# Ref_Mult.net
KiCad netlist of a schematic drawn in Altium Designer
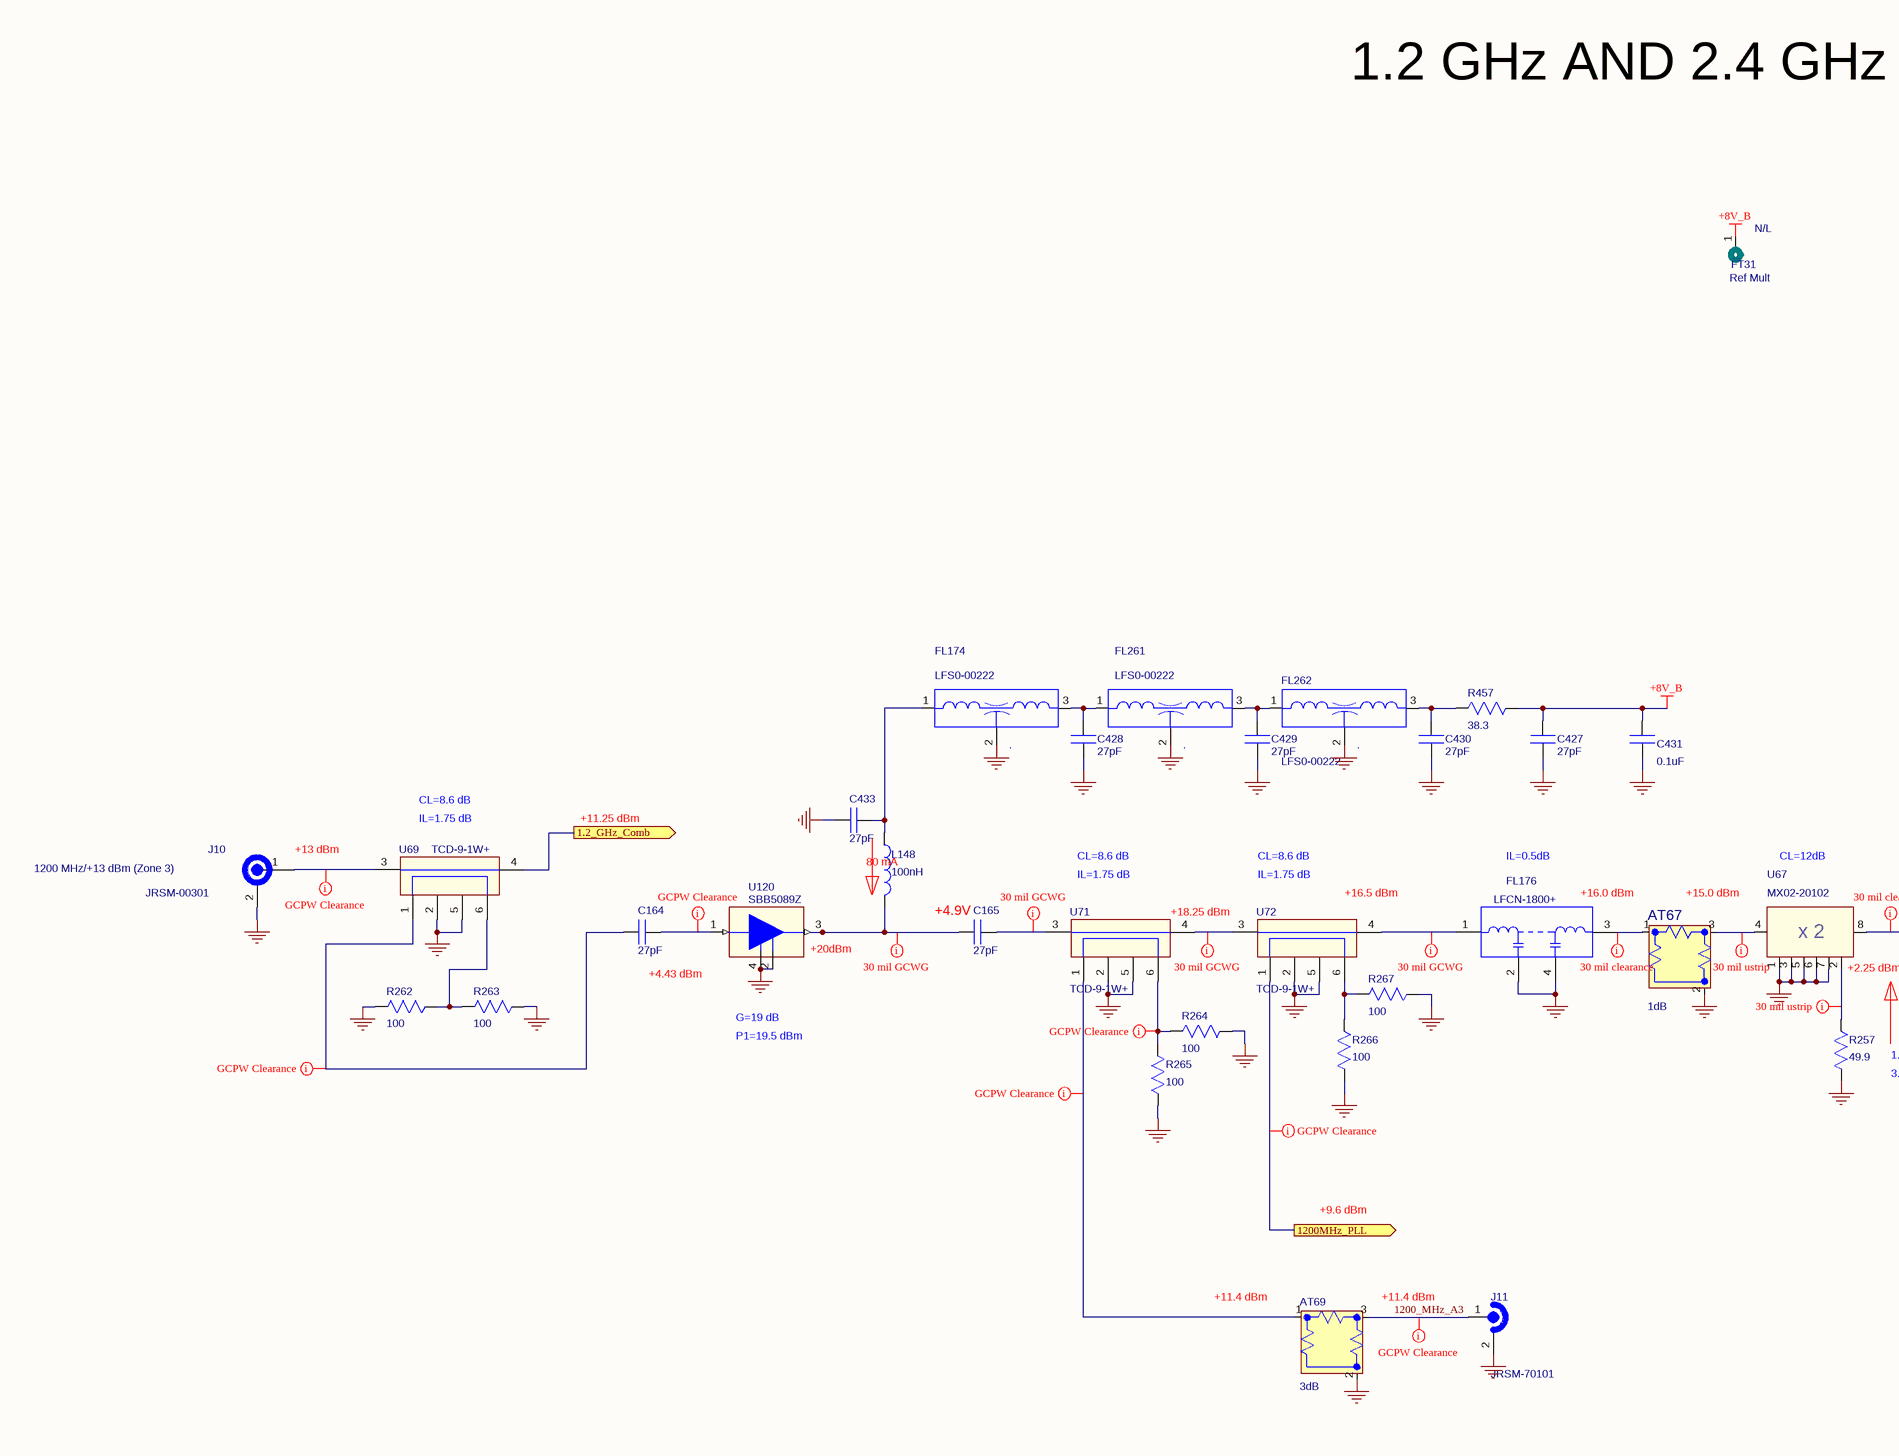
[diagram p0: Ref Mult.SchDoc, left]
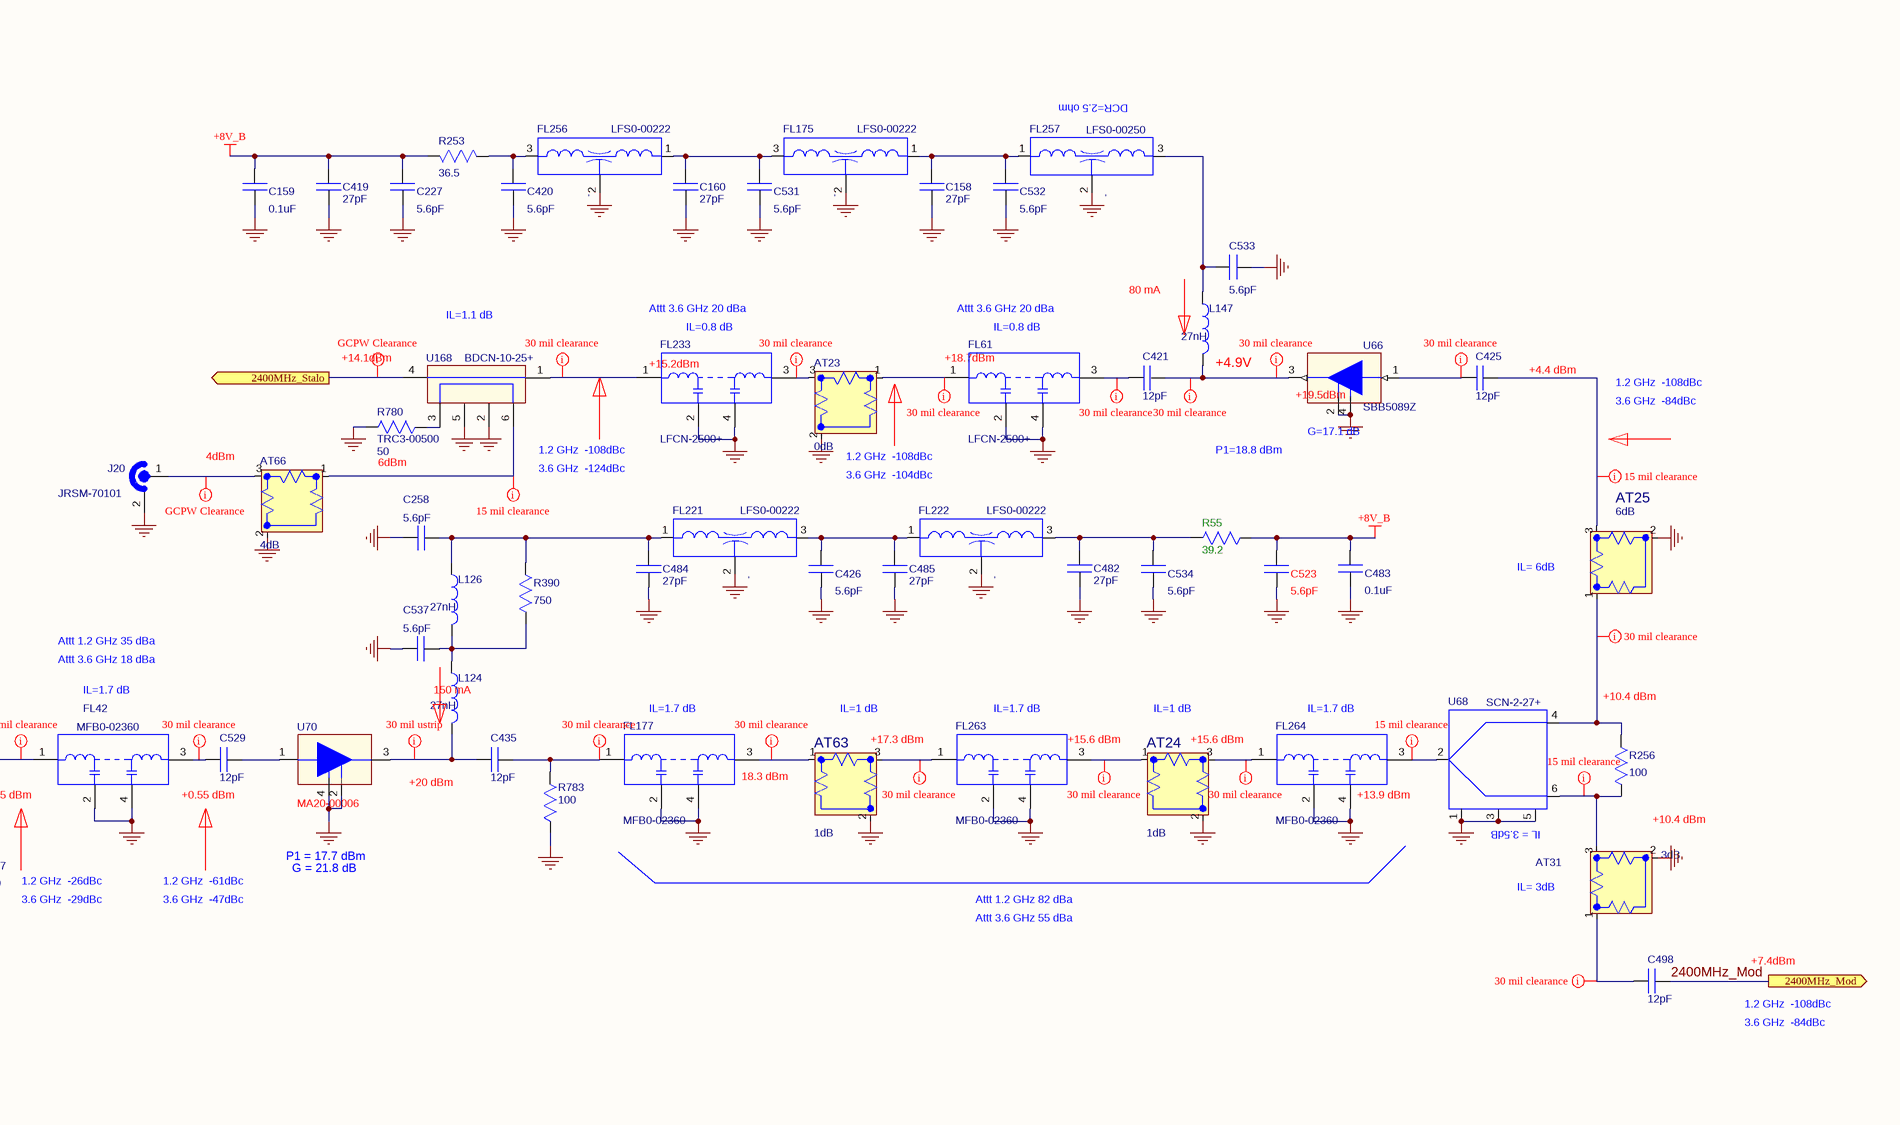
[diagram p1: Ref Mult.SchDoc, right]

(export (version "E")
  (design (tool "Eeschema 10.0.6"))
  (components
    (comp (ref "AT23")
      (value "0dB")
      (footprint "ATTN-IMS-0805")
      (description "PAD;CHIP;0dB;+/-.3dB;.08 x .05;50 OHM;FACE DOWN")
      (fields (field (name "APPROVED") "CL"))
      (libsource (lib "Giga-tronics") (part "MPFC-A1000"))
    )
    (comp (ref "AT24")
      (value "1dB")
      (footprint "ATTN-IMS-0805")
      (description "PAD;CHIP;1dB;+/-.3dB;.08 x .05;50 OHM;FACE DOWN")
      (fields (field (name "APPROVED") "CL"))
      (libsource (lib "Giga-tronics") (part "MPFC-A1001"))
    )
    (comp (ref "AT25")
      (value "6dB")
      (footprint "ATTN-IMS-0805")
      (description "PAD;CHIP;6dB;+/-.3dB;.08 x .05;50 OHM;FACE DOWN")
      (fields (field (name "APPROVED") "CL"))
      (libsource (lib "Giga-tronics") (part "MPFC-A1006"))
    )
    (comp (ref "AT31")
      (value "3dB")
      (footprint "ATTN-IMS-0805")
      (description "PAD;CHIP;3dB;+/-.3dB;.08 x .05;50 OHM;FACE DOWN")
      (fields (field (name "APPROVED") "CL"))
      (libsource (lib "") (part "MPFC-A1003_1"))
    )
    (comp (ref "AT63")
      (value "1dB")
      (footprint "ATTN-IMS-0805")
      (description "PAD;CHIP;1dB;+/-.3dB;.08 x .05;50 OHM;FACE DOWN")
      (fields (field (name "APPROVED") "CL"))
      (libsource (lib "Giga-tronics") (part "MPFC-A1001"))
    )
    (comp (ref "AT66")
      (value "4dB")
      (footprint "ATTN-IMS-0805")
      (description "PAD;CHIP;4dB;+/-.3dB;.08 x .05;50 OHM;FACE DOWN")
      (fields (field (name "APPROVED") "CL"))
      (libsource (lib "Giga-tronics") (part "MPFC-A1004"))
    )
    (comp (ref "AT67")
      (value "1dB")
      (footprint "ATTN-IMS-0805")
      (description "PAD;CHIP;1dB;+/-.3dB;.08 x .05;50 OHM;FACE DOWN")
      (fields (field (name "APPROVED") "CL"))
      (libsource (lib "Giga-tronics") (part "MPFC-A1001"))
    )
    (comp (ref "AT69")
      (value "3dB")
      (footprint "ATTN-IMS-0805")
      (description "PAD;CHIP;3dB;+/-.3dB;.08 x .05;50 OHM;FACE DOWN")
      (fields (field (name "APPROVED") "CL"))
      (libsource (lib "Giga-tronics") (part "MPFC-A1003"))
    )
    (comp (ref "C158")
      (value "27pF")
      (footprint "CAP-0402-N")
      (description "27 PF;5%;COG;>50V;CHIP;0402")
      (fields (field (name "APPROVED") "CL"))
      (libsource (lib "Giga-tronics") (part "CK40-00270"))
    )
    (comp (ref "C159")
      (value "0.1uF")
      (footprint "CAP-0603-H035-N")
      (description ".1UF;10%;X7R;16V;CHIP;0603")
      (fields (field (name "APPROVED") "CL"))
      (libsource (lib "Giga-tronics") (part "CK45-04100"))
    )
    (comp (ref "C160")
      (value "27pF")
      (footprint "CAP-0402-N")
      (description "27 PF;5%;COG;>50V;CHIP;0402")
      (fields (field (name "APPROVED") "CL"))
      (libsource (lib "Giga-tronics") (part "CK40-00270"))
    )
    (comp (ref "C164")
      (value "27pF")
      (footprint "CAP-0402-N")
      (description "27 PF;5%;COG;>50V;CHIP;0402")
      (fields (field (name "APPROVED") "CL"))
      (libsource (lib "Giga-tronics") (part "CK40-00270"))
    )
    (comp (ref "C165")
      (value "27pF")
      (footprint "CAP-0402-N")
      (description "27 PF;5%;COG;>50V;CHIP;0402")
      (fields (field (name "APPROVED") "CL"))
      (libsource (lib "Giga-tronics") (part "CK40-00270"))
    )
    (comp (ref "C227")
      (value "5.6pF")
      (footprint "CAP-0402-RF")
      (description "5.6 PF;200V;.1PF;HIGH Q;SMT;CERAMIC;0402")
      (fields (field (name "APPROVED") "CL"))
      (libsource (lib "Giga-tronics") (part "CK41-00056"))
    )
    (comp (ref "C258")
      (value "5.6pF")
      (footprint "CAP-0402-RF")
      (description "5.6 PF;200V;.1PF;HIGH Q;SMT;CERAMIC;0402")
      (fields (field (name "APPROVED") "CL"))
      (libsource (lib "Giga-tronics") (part "CK41-00056"))
    )
    (comp (ref "C419")
      (value "27pF")
      (footprint "CAP-0402-N")
      (description "27 PF;5%;COG;>50V;CHIP;0402")
      (fields (field (name "APPROVED") "CL"))
      (libsource (lib "Giga-tronics") (part "CK40-00270"))
    )
    (comp (ref "C420")
      (value "5.6pF")
      (footprint "CAP-0402-RF")
      (description "5.6 PF;200V;.1PF;HIGH Q;SMT;CERAMIC;0402")
      (fields (field (name "APPROVED") "CL"))
      (libsource (lib "Giga-tronics") (part "CK41-00056"))
    )
    (comp (ref "C421")
      (value "12pF")
      (footprint "CAP-0402-N")
      (description "12 PF;5%;COG;>50V;CHIP;0402")
      (fields (field (name "APPROVED") "CL"))
      (libsource (lib "Giga-tronics") (part "CK40-00120"))
    )
    (comp (ref "C425")
      (value "12pF")
      (footprint "CAP-0402-N")
      (description "12 PF;5%;COG;>50V;CHIP;0402")
      (fields (field (name "APPROVED") "CL"))
      (libsource (lib "Giga-tronics") (part "CK40-00120"))
    )
    (comp (ref "C426")
      (value "5.6pF")
      (footprint "CAP-0402-RF")
      (description "5.6 PF;200V;.1PF;HIGH Q;SMT;CERAMIC;0402")
      (fields (field (name "APPROVED") "CL"))
      (libsource (lib "Giga-tronics") (part "CK41-00056"))
    )
    (comp (ref "C427")
      (value "27pF")
      (footprint "CAP-0402-N")
      (description "27 PF;5%;COG;>50V;CHIP;0402")
      (fields (field (name "APPROVED") "CL"))
      (libsource (lib "Giga-tronics") (part "CK40-00270"))
    )
    (comp (ref "C428")
      (value "27pF")
      (footprint "CAP-0402-N")
      (description "27 PF;5%;COG;>50V;CHIP;0402")
      (fields (field (name "APPROVED") "CL"))
      (libsource (lib "Giga-tronics") (part "CK40-00270"))
    )
    (comp (ref "C429")
      (value "27pF")
      (footprint "CAP-0402-N")
      (description "27 PF;5%;COG;>50V;CHIP;0402")
      (fields (field (name "APPROVED") "CL"))
      (libsource (lib "Giga-tronics") (part "CK40-00270"))
    )
    (comp (ref "C430")
      (value "27pF")
      (footprint "CAP-0402-N")
      (description "27 PF;5%;COG;>50V;CHIP;0402")
      (fields (field (name "APPROVED") "CL"))
      (libsource (lib "Giga-tronics") (part "CK40-00270"))
    )
    (comp (ref "C431")
      (value "0.1uF")
      (footprint "CAP-0603-H035-N")
      (description ".1UF;10%;X7R;16V;CHIP;0603")
      (fields (field (name "APPROVED") "CL"))
      (libsource (lib "Giga-tronics") (part "CK45-04100"))
    )
    (comp (ref "C433")
      (value "27pF")
      (footprint "CAP-0402-N")
      (description "27 PF;5%;COG;>50V;CHIP;0402")
      (fields (field (name "APPROVED") "CL"))
      (libsource (lib "Giga-tronics") (part "CK40-00270"))
    )
    (comp (ref "C435")
      (value "12pF")
      (footprint "CAP-0402-N")
      (description "12 PF;5%;COG;>50V;CHIP;0402")
      (fields (field (name "APPROVED") "CL"))
      (libsource (lib "Giga-tronics") (part "CK40-00120"))
    )
    (comp (ref "C482")
      (value "27pF")
      (footprint "CAP-0402-N")
      (description "27 PF;5%;COG;>50V;CHIP;0402")
      (fields (field (name "APPROVED") "CL"))
      (libsource (lib "Giga-tronics") (part "CK40-00270"))
    )
    (comp (ref "C483")
      (value "0.1uF")
      (footprint "CAP-0603-H035-N")
      (description ".1UF;10%;X7R;16V;CHIP;0603")
      (fields (field (name "APPROVED") "CL"))
      (libsource (lib "Giga-tronics") (part "CK45-04100"))
    )
    (comp (ref "C484")
      (value "27pF")
      (footprint "CAP-0402-N")
      (description "27 PF;5%;COG;>50V;CHIP;0402")
      (fields (field (name "APPROVED") "CL"))
      (libsource (lib "Giga-tronics") (part "CK40-00270"))
    )
    (comp (ref "C485")
      (value "27pF")
      (footprint "CAP-0402-N")
      (description "27 PF;5%;COG;>50V;CHIP;0402")
      (fields (field (name "APPROVED") "CL"))
      (libsource (lib "Giga-tronics") (part "CK40-00270"))
    )
    (comp (ref "C498")
      (value "12pF")
      (footprint "CAP-0402-N")
      (description "12 PF;5%;COG;>50V;CHIP;0402")
      (fields (field (name "APPROVED") "CL"))
      (libsource (lib "Giga-tronics") (part "CK40-00120"))
    )
    (comp (ref "C523")
      (value "5.6pF")
      (footprint "CAP-0402-RF")
      (description "5.6 PF;200V;.1PF;HIGH Q;SMT;CERAMIC;0402")
      (fields (field (name "APPROVED") "CL"))
      (libsource (lib "Giga-tronics") (part "CK41-00056"))
    )
    (comp (ref "C529")
      (value "12pF")
      (footprint "CAP-0402-N")
      (description "12 PF;5%;COG;>50V;CHIP;0402")
      (fields (field (name "APPROVED") "CL"))
      (libsource (lib "Giga-tronics") (part "CK40-00120"))
    )
    (comp (ref "C531")
      (value "5.6pF")
      (footprint "CAP-0402-RF")
      (description "5.6 PF;200V;.1PF;HIGH Q;SMT;CERAMIC;0402")
      (fields (field (name "APPROVED") "CL"))
      (libsource (lib "Giga-tronics") (part "CK41-00056"))
    )
    (comp (ref "C532")
      (value "5.6pF")
      (footprint "CAP-0402-RF")
      (description "5.6 PF;200V;.1PF;HIGH Q;SMT;CERAMIC;0402")
      (fields (field (name "APPROVED") "CL"))
      (libsource (lib "Giga-tronics") (part "CK41-00056"))
    )
    (comp (ref "C533")
      (value "5.6pF")
      (footprint "CAP-0402-RF")
      (description "5.6 PF;200V;.1PF;HIGH Q;SMT;CERAMIC;0402")
      (fields (field (name "APPROVED") "CL"))
      (libsource (lib "Giga-tronics") (part "CK41-00056"))
    )
    (comp (ref "C534")
      (value "5.6pF")
      (footprint "CAP-0402-RF")
      (description "5.6 PF;200V;.1PF;HIGH Q;SMT;CERAMIC;0402")
      (fields (field (name "APPROVED") "CL"))
      (libsource (lib "Giga-tronics") (part "CK41-00056"))
    )
    (comp (ref "C537")
      (value "5.6pF")
      (footprint "CAP-0402-RF")
      (description "5.6 PF;200V;.1PF;HIGH Q;SMT;CERAMIC;0402")
      (fields (field (name "APPROVED") "CL"))
      (libsource (lib "Giga-tronics") (part "CK41-00056"))
    )
    (comp (ref "FL42")
      (value "2360 MHZ BANDPASS FILTER 220 MHZ BW;3.2X1.3mm;FV1206;4 PIN")
      (footprint "FV1206")
      (fields (field (name "G_PN") "MFB0-02360") (field (name "APPROVED") "NM"))
      (libsource (lib "Giga-tronics") (part "MFB0-02360"))
    )
    (comp (ref "FL61")
      (value "FILTER;LOW PASS;2.500GHZ;5 SECTIONS;1A;1206")
      (footprint "FV1206")
      (fields (field (name "M_PN") "LFCN-2500+") (field (name "APPROVED") "CL"))
      (libsource (lib "Giga-tronics") (part "MFL0-02500"))
    )
    (comp (ref "FL174")
      (value "Filter EMI 2200PF,1206")
      (footprint "FIL-NFE31P-1206-4P")
      (fields (field (name "G_PN") "LFS0-00222") (field (name "APPROVED") "CL"))
      (libsource (lib "Giga-tronics") (part "LFS0-00222"))
    )
    (comp (ref "FL175")
      (value "Filter EMI 2200PF,1206")
      (footprint "FIL-NFE31P-1206-4P")
      (fields (field (name "G_PN") "LFS0-00222") (field (name "APPROVED") "CL"))
      (libsource (lib "") (part "LFS0-00222_1"))
    )
    (comp (ref "FL176")
      (value "FILTER;LOW PASS;1800MHZ;7SECTIONS;10W;FV1206;RoHS")
      (footprint "FV1206")
      (fields (field (name "M_PN") "LFCN-1800+") (field (name "APPROVED") "NM"))
      (libsource (lib "Giga-tronics") (part "MFL0-01800"))
    )
    (comp (ref "FL177")
      (value "2360 MHZ BANDPASS FILTER 220 MHZ BW;3.2X1.3mm;FV1206;4 PIN")
      (footprint "FV1206")
      (fields (field (name "G_PN") "MFB0-02360") (field (name "APPROVED") "NM"))
      (libsource (lib "Giga-tronics") (part "MFB0-02360"))
    )
    (comp (ref "FL221")
      (value "Filter EMI 2200PF,1206")
      (footprint "FIL-NFE31P-1206-4P")
      (fields (field (name "G_PN") "LFS0-00222") (field (name "APPROVED") "CL"))
      (libsource (lib "Giga-tronics") (part "LFS0-00222"))
    )
    (comp (ref "FL222")
      (value "Filter EMI 2200PF,1206")
      (footprint "FIL-NFE31P-1206-4P")
      (fields (field (name "G_PN") "LFS0-00222") (field (name "APPROVED") "CL"))
      (libsource (lib "Giga-tronics") (part "LFS0-00222"))
    )
    (comp (ref "FL233")
      (value "FILTER;LOW PASS;2.500GHZ;5 SECTIONS;1A;1206")
      (footprint "FV1206")
      (fields (field (name "M_PN") "LFCN-2500+") (field (name "APPROVED") "CL"))
      (libsource (lib "Giga-tronics") (part "MFL0-02500"))
    )
    (comp (ref "FL256")
      (value "Filter EMI 2200PF,1206")
      (footprint "FIL-NFE31P-1206-4P")
      (fields (field (name "G_PN") "LFS0-00222") (field (name "APPROVED") "CL"))
      (libsource (lib "") (part "LFS0-00222_1"))
    )
    (comp (ref "FL257")
      (value "F/T FILTER;CHIP;2.5 DCR150MA;16V;T LC;25PF;200MHz;0603")
      (footprint "FIL-NFL18ST")
      (fields (field (name "G_PN") "LFS0-00250") (field (name "APPROVED") "NM"))
      (libsource (lib "Giga-tronics") (part "LFS0-00250"))
    )
    (comp (ref "FL261")
      (value "Filter EMI 2200PF,1206")
      (footprint "FIL-NFE31P-1206-4P")
      (fields (field (name "G_PN") "LFS0-00222") (field (name "APPROVED") "CL"))
      (libsource (lib "Giga-tronics") (part "LFS0-00222"))
    )
    (comp (ref "FL262")
      (value "Filter EMI 2200PF,1206")
      (footprint "FIL-NFE31P-1206-4P")
      (fields (field (name "G_PN") "LFS0-00222") (field (name "APPROVED") "CL"))
      (libsource (lib "Giga-tronics") (part "LFS0-00222"))
    )
    (comp (ref "FL263")
      (value "2360 MHZ BANDPASS FILTER 220 MHZ BW;3.2X1.3mm;FV1206;4 PIN")
      (footprint "FV1206")
      (fields (field (name "G_PN") "MFB0-02360") (field (name "APPROVED") "NM"))
      (libsource (lib "Giga-tronics") (part "MFB0-02360"))
    )
    (comp (ref "FL264")
      (value "2360 MHZ BANDPASS FILTER 220 MHZ BW;3.2X1.3mm;FV1206;4 PIN")
      (footprint "FV1206")
      (fields (field (name "G_PN") "MFB0-02360") (field (name "APPROVED") "NM"))
      (libsource (lib "Giga-tronics") (part "MFB0-02360"))
    )
    (comp (ref "FT31")
      (value "Ref Mult")
      (footprint "FromToNode_ML2")
      (fields (field (name "NOLOAD") "N/L") (field (name "APPROVED") "*"))
      (libsource (lib "Giga-tronics") (part "FromToNode"))
    )
    (comp (ref "J10")
      (value "1200 MHz/+13 dBm (Zone 3)")
      (footprint "CONN-3211-60035_plane_cutout")
      (description "SMPM;SB EDGE LAUNCH;MALE;1 PORT")
      (fields (field (name "G_PN") "JRSM-00301") (field (name "APPROVED") "CL"))
      (libsource (lib "Giga-tronics") (part "JRSM-00301"))
    )
    (comp (ref "J11")
      (value ".")
      (footprint "JRSM-70101")
      (description "SMPM FD MALE,STRAIGHT SMT, R/A COPLANAR, 4 PIN THRU-HOLE")
      (fields (field (name "G_PN") "JRSM-70101") (field (name "APPROVED") "CL"))
      (libsource (lib "") (part "JRSM-70101_1"))
    )
    (comp (ref "J20")
      (value ".")
      (footprint "JRSM-70101")
      (description "SMPM FD MALE,STRAIGHT SMT, R/A COPLANAR, 4 PIN THRU-HOLE")
      (fields (field (name "G_PN") "JRSM-70101") (field (name "APPROVED") "CL"))
      (libsource (lib "Giga-tronics") (part "JRSM-70101"))
    )
    (comp (ref "L124")
      (value "27nH")
      (footprint "IND-0603HP")
      (description "INDUCTOR;27NH;2%;2.8G SRF;74Q @0.9G;.150DCR;.78A;0603")
      (fields (field (name "APPROVED") "CL"))
      (libsource (lib "Giga-tronics") (part "LSA5-03270"))
    )
    (comp (ref "L126")
      (value "27nH")
      (footprint "IND-0603HP")
      (description "INDUCTOR;27NH;2%;2.8G SRF;74Q @0.9G;.150DCR;.78A;0603")
      (fields (field (name "APPROVED") "CL"))
      (libsource (lib "Giga-tronics") (part "LSA5-03270"))
    )
    (comp (ref "L147")
      (value "27nH")
      (footprint "IND-0603HP")
      (description "INDUCTOR;27NH;2%;2.8G SRF;74Q @0.9G;.150DCR;.78A;0603")
      (fields (field (name "APPROVED") "CL"))
      (libsource (lib "Giga-tronics") (part "LSA5-03270"))
    )
    (comp (ref "L148")
      (value "100nH")
      (footprint "IND-0603CS")
      (description "INDUCTOR;100NH;5%;1.4GHZ SRF;34Q;.58 DCR;400MA;WIREWOUND;0603")
      (fields (field (name "APPROVED") "CL"))
      (libsource (lib "Giga-tronics") (part "LSA3-14100"))
    )
    (comp (ref "R55")
      (value "39.2")
      (footprint "RES-2010-N")
      (description "39.2 OHM;.75W;1%;100PPM;FILM CHIP;2010")
      (fields (field (name "APPROVED") "CL"))
      (libsource (lib "Giga-tronics") (part "RK65-00392"))
    )
    (comp (ref "R253")
      (value "36.5")
      (footprint "RES-2010-N")
      (description "36.5 OHM;.75W;1%;100PPM;FILM CHIP;2010")
      (fields (field (name "APPROVED") "CL"))
      (libsource (lib "Giga-tronics") (part "RK65-00365"))
    )
    (comp (ref "R256")
      (value "100")
      (footprint "RES-0603-N")
      (description "100 OHMS; 1%; .1W; 100PPM; FILM; CHIP; 0603")
      (fields (field (name "APPROVED") "CL"))
      (libsource (lib "Giga-tronics") (part "RK40-01000"))
    )
    (comp (ref "R257")
      (value "49.9")
      (footprint "RES-0402-N")
      (description "49.9 OHMS;.06W;1%;200PPM;FILM;CHIP;0402")
      (fields (field (name "APPROVED") "CL"))
      (libsource (lib "Giga-tronics") (part "RK35-00499"))
    )
    (comp (ref "R262")
      (value "100")
      (footprint "RES-0402-N")
      (description "100 OHMS; 1%; .1W; 100PPM; FILM; CHIP; 0402")
      (fields (field (name "APPROVED") "CL"))
      (libsource (lib "Giga-tronics") (part "RK35-01000"))
    )
    (comp (ref "R263")
      (value "100")
      (footprint "RES-0402-N")
      (description "100 OHMS; 1%; .1W; 100PPM; FILM; CHIP; 0402")
      (fields (field (name "APPROVED") "CL"))
      (libsource (lib "Giga-tronics") (part "RK35-01000"))
    )
    (comp (ref "R264")
      (value "100")
      (footprint "RES-0402-N")
      (description "100 OHMS; 1%; .1W; 100PPM; FILM; CHIP; 0402")
      (fields (field (name "APPROVED") "CL"))
      (libsource (lib "Giga-tronics") (part "RK35-01000"))
    )
    (comp (ref "R265")
      (value "100")
      (footprint "RES-0402-N")
      (description "100 OHMS; 1%; .1W; 100PPM; FILM; CHIP; 0402")
      (fields (field (name "APPROVED") "CL"))
      (libsource (lib "Giga-tronics") (part "RK35-01000"))
    )
    (comp (ref "R266")
      (value "100")
      (footprint "RES-0402-N")
      (description "100 OHMS; 1%; .1W; 100PPM; FILM; CHIP; 0402")
      (fields (field (name "APPROVED") "CL"))
      (libsource (lib "Giga-tronics") (part "RK35-01000"))
    )
    (comp (ref "R267")
      (value "100")
      (footprint "RES-0402-N")
      (description "100 OHMS; 1%; .1W; 100PPM; FILM; CHIP; 0402")
      (fields (field (name "APPROVED") "CL"))
      (libsource (lib "Giga-tronics") (part "RK35-01000"))
    )
    (comp (ref "R390")
      (value "750")
      (footprint "RES-0402-N")
      (description "750 OHMS;.1W;1%;100PPM;FILM CHIP;0402")
      (fields (field (name "APPROVED") "CL"))
      (libsource (lib "Giga-tronics") (part "RK35-07500"))
    )
    (comp (ref "R457")
      (value "38.3")
      (footprint "RES-2010-N")
      (description "38.3 OHM;.75W;1%;100PPM;FILM CHIP;2010")
      (fields (field (name "APPROVED") "CL"))
      (libsource (lib "Giga-tronics") (part "RK65-00383"))
    )
    (comp (ref "R780")
      (value "50")
      (footprint "RES-0402-N")
      (description "RES;50 OHM;CHIP;5%;250PPM;PART WRAP;0402")
      (fields (field (name "G_PN") "TRC3-00500") (field (name "APPROVED") "CL"))
      (libsource (lib "Giga-tronics") (part "TRC3-00500"))
    )
    (comp (ref "R783")
      (value "100")
      (footprint "RES-0201-N")
      (description "100 OHMS;.05W;1%;100PPM;FILM CHIP;0201")
      (fields (field (name "APPROVED") "CL"))
      (libsource (lib "Giga-tronics") (part "RK30-01000"))
    )
    (comp (ref "U66")
      (value "AMP;.05-6GHZ;+21DBM;5V;75MA;SOT-89; RoHS")
      (footprint "SOT-89")
      (fields (field (name "M_PN") "SBB5089Z") (field (name "APPROVED") "XiaoXiao"))
      (libsource (lib "Giga-tronics") (part "MA21-00006"))
    )
    (comp (ref "U67")
      (value "DOUBLER;850-2000 MHZ IN;15DB CONV LOSS;10-20DBM IN;SO-8")
      (footprint "HV1195")
      (fields (field (name "G_PN") "MX02-20102") (field (name "APPROVED") "CL"))
      (libsource (lib "Giga-tronics") (part "MX02-20102"))
    )
    (comp (ref "U68")
      (value "LRPS-2-1J+")
      (footprint "FV1206-1-PS")
      (description "POWER SPLITTER/COMBINER;2225-2700 MHZ;0 DEG;FV1206-1 CASE")
      (fields (field (name "M_PN") "SCN-2-27+") (field (name "APPROVED") "CL"))
      (libsource (lib "Giga-tronics") (part "MZD1-S0002"))
    )
    (comp (ref "U69")
      (value "COUPLER;8.9DB;5-2000 MHZ;1.2DB LOSS;DB714 SMT CASE")
      (footprint "CPLR-DB714")
      (fields (field (name "M_PN") "TCD-9-1W+") (field (name "APPROVED") "CL"))
      (libsource (lib "Giga-tronics") (part "MC09-00002"))
    )
    (comp (ref "U70")
      (value "AMP;0-6GHZ;20DB;+20DBM;5V;100MA;SOT-89")
      (footprint "SOT-89")
      (fields (field (name "G_PN") "MA20-00006") (field (name "APPROVED") "CL"))
      (libsource (lib "Giga-tronics") (part "MA20-00006"))
    )
    (comp (ref "U71")
      (value "COUPLER;8.9DB;5-2000 MHZ;1.2DB LOSS;DB714 SMT CASE")
      (footprint "CPLR-DB714")
      (fields (field (name "M_PN") "TCD-9-1W+") (field (name "APPROVED") "CL"))
      (libsource (lib "Giga-tronics") (part "MC09-00002"))
    )
    (comp (ref "U72")
      (value "COUPLER;8.9DB;5-2000 MHZ;1.2DB LOSS;DB714 SMT CASE")
      (footprint "CPLR-DB714")
      (fields (field (name "M_PN") "TCD-9-1W+") (field (name "APPROVED") "CL"))
      (libsource (lib "Giga-tronics") (part "MC09-00002"))
    )
    (comp (ref "U120")
      (value "AMP;.05-6GHZ;+21DBM;5V;75MA;SOT-89; RoHS")
      (footprint "SOT-89")
      (fields (field (name "M_PN") "SBB5089Z") (field (name "APPROVED") "XiaoXiao"))
      (libsource (lib "") (part "MA21-00006_1"))
    )
    (comp (ref "U168")
      (value "COUPLER;10DB;820-2525 MHZ;1.5DB LOSS;FV1206-1 SMT CASE")
      (footprint "FV1206-1-PS")
      (fields (field (name "M_PN") "BDCN-10-25+") (field (name "APPROVED") "CL"))
      (libsource (lib "Giga-tronics") (part "MC10-00103"))
    )
  )
  (nets
    (net (code "1") (name "+8V_B") (class "Default")
      (node (ref "C159") (pin "1") (pintype "passive"))
      (node (ref "C227") (pin "1") (pintype "passive"))
      (node (ref "C419") (pin "1") (pintype "passive"))
      (node (ref "C427") (pin "1") (pintype "passive"))
      (node (ref "C431") (pin "1") (pintype "passive"))
      (node (ref "C483") (pin "1") (pintype "passive"))
      (node (ref "C523") (pin "2") (pintype "passive"))
      (node (ref "FT31") (pin "1") (pinfunction "1_1") (pintype "passive"))
      (node (ref "R253") (pin "2") (pintype "passive"))
      (node (ref "R457") (pin "1") (pintype "passive"))
      (node (ref "R55") (pin "2") (pintype "passive"))
    )
    (net (code "2") (name "/1.2_GHz_Comb") (class "Default")
      (node (ref "U69") (pin "4") (pinfunction "4_4") (pintype "passive"))
    )
    (net (code "3") (name "/1200MHz_PLL") (class "Default")
      (node (ref "U72") (pin "1") (pinfunction "1_1") (pintype "passive"))
    )
    (net (code "4") (name "/1200_MHz_A3") (class "Default")
      (node (ref "AT69") (pin "3") (pinfunction "IN/OUT_3") (pintype "passive"))
      (node (ref "J11") (pin "1") (pinfunction "CNTR_1") (pintype "passive"))
    )
    (net (code "5") (name "/2400MHz_Mod") (class "Default") (node (ref "C498") (pin "2") (pintype "passive")))
    (net (code "6") (name "/2400MHz_Stalo") (class "Default")
      (node (ref "U168") (pin "4") (pinfunction "OUTPUT_4") (pintype "passive"))
    )
    (net (code "7") (name "GND") (class "Default")
      (node (ref "AT23") (pin "2") (pinfunction "GND_2") (pintype "power_in"))
      (node (ref "AT24") (pin "2") (pinfunction "GND_2") (pintype "power_in"))
      (node (ref "AT25") (pin "2") (pinfunction "GND_2") (pintype "power_in"))
      (node (ref "AT31") (pin "2") (pinfunction "GND_2") (pintype "power_in"))
      (node (ref "AT63") (pin "2") (pinfunction "GND_2") (pintype "power_in"))
      (node (ref "AT66") (pin "2") (pinfunction "GND_2") (pintype "power_in"))
      (node (ref "AT67") (pin "2") (pinfunction "GND_2") (pintype "power_in"))
      (node (ref "AT69") (pin "2") (pinfunction "GND_2") (pintype "power_in"))
      (node (ref "C158") (pin "2") (pintype "passive"))
      (node (ref "C159") (pin "2") (pintype "passive"))
      (node (ref "C160") (pin "2") (pintype "passive"))
      (node (ref "C227") (pin "2") (pintype "passive"))
      (node (ref "C258") (pin "2") (pintype "passive"))
      (node (ref "C419") (pin "2") (pintype "passive"))
      (node (ref "C420") (pin "2") (pintype "passive"))
      (node (ref "C426") (pin "1") (pintype "passive"))
      (node (ref "C427") (pin "2") (pintype "passive"))
      (node (ref "C428") (pin "2") (pintype "passive"))
      (node (ref "C429") (pin "2") (pintype "passive"))
      (node (ref "C430") (pin "2") (pintype "passive"))
      (node (ref "C431") (pin "2") (pintype "passive"))
      (node (ref "C433") (pin "2") (pintype "passive"))
      (node (ref "C482") (pin "2") (pintype "passive"))
      (node (ref "C483") (pin "2") (pintype "passive"))
      (node (ref "C484") (pin "1") (pintype "passive"))
      (node (ref "C485") (pin "1") (pintype "passive"))
      (node (ref "C523") (pin "1") (pintype "passive"))
      (node (ref "C531") (pin "2") (pintype "passive"))
      (node (ref "C532") (pin "2") (pintype "passive"))
      (node (ref "C533") (pin "2") (pintype "passive"))
      (node (ref "C534") (pin "1") (pintype "passive"))
      (node (ref "C537") (pin "1") (pintype "passive"))
      (node (ref "FL174") (pin "2") (pinfunction "GND_2") (pintype "passive"))
      (node (ref "FL175") (pin "2") (pinfunction "GND_2") (pintype "passive"))
      (node (ref "FL176") (pin "2") (pinfunction "GND_2") (pintype "passive"))
      (node (ref "FL176") (pin "4") (pinfunction "GND_4") (pintype "passive"))
      (node (ref "FL177") (pin "2") (pinfunction "GND_2") (pintype "passive"))
      (node (ref "FL177") (pin "4") (pinfunction "GND_4") (pintype "passive"))
      (node (ref "FL221") (pin "2") (pinfunction "GND_2") (pintype "passive"))
      (node (ref "FL222") (pin "2") (pinfunction "GND_2") (pintype "passive"))
      (node (ref "FL233") (pin "2") (pinfunction "GND_2") (pintype "passive"))
      (node (ref "FL233") (pin "4") (pinfunction "GND_4") (pintype "passive"))
      (node (ref "FL256") (pin "2") (pinfunction "GND_2") (pintype "passive"))
      (node (ref "FL257") (pin "2") (pinfunction "GND_2") (pintype "passive"))
      (node (ref "FL261") (pin "2") (pinfunction "GND_2") (pintype "passive"))
      (node (ref "FL262") (pin "2") (pinfunction "GND_2") (pintype "passive"))
      (node (ref "FL263") (pin "2") (pinfunction "GND_2") (pintype "passive"))
      (node (ref "FL263") (pin "4") (pinfunction "GND_4") (pintype "passive"))
      (node (ref "FL264") (pin "2") (pinfunction "GND_2") (pintype "passive"))
      (node (ref "FL264") (pin "4") (pinfunction "GND_4") (pintype "passive"))
      (node (ref "FL42") (pin "2") (pinfunction "GND_2") (pintype "passive"))
      (node (ref "FL42") (pin "4") (pinfunction "GND_4") (pintype "passive"))
      (node (ref "FL61") (pin "2") (pinfunction "GND_2") (pintype "passive"))
      (node (ref "FL61") (pin "4") (pinfunction "GND_4") (pintype "passive"))
      (node (ref "J10") (pin "2") (pinfunction "GND_2") (pintype "passive"))
      (node (ref "J11") (pin "2") (pinfunction "GND_2") (pintype "passive"))
      (node (ref "J20") (pin "2") (pinfunction "GND_2") (pintype "passive"))
      (node (ref "R257") (pin "1") (pintype "passive"))
      (node (ref "R262") (pin "1") (pintype "passive"))
      (node (ref "R263") (pin "2") (pintype "passive"))
      (node (ref "R264") (pin "1") (pintype "passive"))
      (node (ref "R265") (pin "2") (pintype "passive"))
      (node (ref "R266") (pin "1") (pintype "passive"))
      (node (ref "R267") (pin "2") (pintype "passive"))
      (node (ref "R780") (pin "1") (pintype "passive"))
      (node (ref "R783") (pin "1") (pintype "passive"))
      (node (ref "U120") (pin "2") (pinfunction "GND_2") (pintype "power_in"))
      (node (ref "U120") (pin "4") (pinfunction "GND_4") (pintype "power_in"))
      (node (ref "U168") (pin "2") (pinfunction "GND_2") (pintype "passive"))
      (node (ref "U168") (pin "5") (pinfunction "GND_5") (pintype "passive"))
      (node (ref "U66") (pin "2") (pinfunction "GND_2") (pintype "power_in"))
      (node (ref "U66") (pin "4") (pinfunction "GND_4") (pintype "power_in"))
      (node (ref "U67") (pin "1") (pinfunction "GND_1") (pintype "passive"))
      (node (ref "U67") (pin "3") (pinfunction "GND_3") (pintype "passive"))
      (node (ref "U67") (pin "5") (pinfunction "GND_5") (pintype "passive"))
      (node (ref "U67") (pin "6") (pinfunction "GND_6") (pintype "passive"))
      (node (ref "U67") (pin "7") (pinfunction "GND_7") (pintype "passive"))
      (node (ref "U68") (pin "1") (pinfunction "GND_1") (pintype "passive"))
      (node (ref "U68") (pin "3") (pinfunction "GND_3") (pintype "passive"))
      (node (ref "U68") (pin "5") (pinfunction "GND_5") (pintype "passive"))
      (node (ref "U69") (pin "2") (pinfunction "2_2") (pintype "passive"))
      (node (ref "U69") (pin "5") (pinfunction "5_5") (pintype "passive"))
      (node (ref "U70") (pin "2") (pinfunction "GND_2") (pintype "passive"))
      (node (ref "U70") (pin "4") (pinfunction "4_4") (pintype "passive"))
      (node (ref "U71") (pin "2") (pinfunction "2_2") (pintype "passive"))
      (node (ref "U71") (pin "5") (pinfunction "5_5") (pintype "passive"))
      (node (ref "U72") (pin "2") (pinfunction "2_2") (pintype "passive"))
      (node (ref "U72") (pin "5") (pinfunction "5_5") (pintype "passive"))
    )
    (net (code "8") (name "Net-(AT25-IN{slash}OUT-Pad1)") (class "Default")
      (node (ref "AT25") (pin "1") (pinfunction "IN/OUT_1") (pintype "passive"))
      (node (ref "R256") (pin "2") (pintype "passive"))
      (node (ref "U68") (pin "4") (pintype "passive"))
    )
    (net (code "9") (name "Net-(AT25-IN{slash}OUT-Pad3)") (class "Default")
      (node (ref "AT25") (pin "3") (pinfunction "IN/OUT_3") (pintype "passive"))
      (node (ref "C425") (pin "1") (pintype "passive"))
    )
    (net (code "10") (name "Net-(AT31-IN{slash}OUT-Pad1)") (class "Default")
      (node (ref "AT31") (pin "1") (pinfunction "IN/OUT_1") (pintype "passive"))
      (node (ref "C498") (pin "1") (pintype "passive"))
    )
    (net (code "11") (name "Net-(AT31-IN{slash}OUT-Pad3)") (class "Default")
      (node (ref "AT31") (pin "3") (pinfunction "IN/OUT_3") (pintype "passive"))
      (node (ref "R256") (pin "1") (pintype "passive"))
      (node (ref "U68") (pin "6") (pintype "passive"))
    )
    (net (code "12") (name "Net-(AT69-IN{slash}OUT-Pad1)") (class "Default")
      (node (ref "AT69") (pin "1") (pinfunction "IN/OUT_1") (pintype "passive"))
      (node (ref "U71") (pin "1") (pinfunction "1_1") (pintype "passive"))
    )
    (net (code "13") (name "Net-(C164-Pad1)") (class "Default")
      (node (ref "C164") (pin "1") (pintype "passive"))
      (node (ref "U69") (pin "1") (pinfunction "1_1") (pintype "passive"))
    )
    (net (code "14") (name "Net-(C165-Pad2)") (class "Default")
      (node (ref "C165") (pin "2") (pintype "passive"))
      (node (ref "U71") (pin "3") (pinfunction "3_3") (pintype "passive"))
    )
    (net (code "15") (name "Net-(C435-Pad1)") (class "Default")
      (node (ref "C435") (pin "1") (pintype "passive"))
      (node (ref "L124") (pin "1") (pinfunction "1_1") (pintype "passive"))
      (node (ref "U70") (pin "3") (pinfunction "3_3") (pintype "passive"))
    )
    (net (code "16") (name "Net-(C529-Pad2)") (class "Default")
      (node (ref "C529") (pin "2") (pintype "passive"))
      (node (ref "U70") (pin "1") (pinfunction "1_1") (pintype "passive"))
    )
    (net (code "17") (name "Net-(C537-Pad2)") (class "Default")
      (node (ref "C537") (pin "2") (pintype "passive"))
      (node (ref "L124") (pin "2") (pinfunction "2_2") (pintype "passive"))
      (node (ref "L126") (pin "1") (pinfunction "1_1") (pintype "passive"))
      (node (ref "R390") (pin "1") (pintype "passive"))
    )
    (net (code "18") (name "Net-(FL42-IN)") (class "Default")
      (node (ref "FL42") (pin "1") (pinfunction "IN_1") (pintype "passive"))
      (node (ref "U67") (pin "8") (pinfunction "OUT_8") (pintype "passive"))
    )
    (net (code "19") (name "Net-(FL42-OUT)") (class "Default")
      (node (ref "C529") (pin "1") (pintype "passive"))
      (node (ref "FL42") (pin "3") (pinfunction "OUT_3") (pintype "passive"))
    )
    (net (code "20") (name "Net-(FL61-IN)") (class "Default")
      (node (ref "AT23") (pin "1") (pinfunction "IN/OUT_1") (pintype "passive"))
      (node (ref "FL61") (pin "1") (pinfunction "IN_1") (pintype "passive"))
    )
    (net (code "21") (name "Net-(FL61-OUT)") (class "Default")
      (node (ref "C421") (pin "1") (pintype "passive"))
      (node (ref "FL61") (pin "3") (pinfunction "OUT_3") (pintype "passive"))
    )
    (net (code "22") (name "Net-(FL174-IN)") (class "Default")
      (node (ref "C433") (pin "1") (pintype "passive"))
      (node (ref "FL174") (pin "1") (pinfunction "IN_1") (pintype "passive"))
      (node (ref "L148") (pin "2") (pinfunction "2_2") (pintype "passive"))
    )
    (net (code "23") (name "Net-(FL174-OUT)") (class "Default")
      (node (ref "C428") (pin "1") (pintype "passive"))
      (node (ref "FL174") (pin "3") (pinfunction "OUT_3") (pintype "passive"))
      (node (ref "FL261") (pin "1") (pinfunction "IN_1") (pintype "passive"))
    )
    (net (code "24") (name "Net-(FL175-IN)") (class "Default")
      (node (ref "C158") (pin "1") (pintype "passive"))
      (node (ref "C532") (pin "1") (pintype "passive"))
      (node (ref "FL175") (pin "1") (pinfunction "IN_1") (pintype "passive"))
      (node (ref "FL257") (pin "1") (pinfunction "IN_1") (pintype "passive"))
    )
    (net (code "25") (name "Net-(FL175-OUT)") (class "Default")
      (node (ref "C160") (pin "1") (pintype "passive"))
      (node (ref "C531") (pin "1") (pintype "passive"))
      (node (ref "FL175") (pin "3") (pinfunction "OUT_3") (pintype "passive"))
      (node (ref "FL256") (pin "1") (pinfunction "IN_1") (pintype "passive"))
    )
    (net (code "26") (name "Net-(FL176-IN)") (class "Default")
      (node (ref "FL176") (pin "1") (pinfunction "IN_1") (pintype "passive"))
      (node (ref "U72") (pin "4") (pinfunction "4_4") (pintype "passive"))
    )
    (net (code "27") (name "Net-(FL176-OUT)") (class "Default")
      (node (ref "AT67") (pin "1") (pinfunction "IN/OUT_1") (pintype "passive"))
      (node (ref "FL176") (pin "3") (pinfunction "OUT_3") (pintype "passive"))
    )
    (net (code "28") (name "Net-(FL177-IN)") (class "Default")
      (node (ref "C435") (pin "2") (pintype "passive"))
      (node (ref "FL177") (pin "1") (pinfunction "IN_1") (pintype "passive"))
      (node (ref "R783") (pin "2") (pintype "passive"))
    )
    (net (code "29") (name "Net-(FL177-OUT)") (class "Default")
      (node (ref "AT63") (pin "1") (pinfunction "IN/OUT_1") (pintype "passive"))
      (node (ref "FL177") (pin "3") (pinfunction "OUT_3") (pintype "passive"))
    )
    (net (code "30") (name "Net-(FL221-IN)") (class "Default")
      (node (ref "C258") (pin "1") (pintype "passive"))
      (node (ref "C484") (pin "2") (pintype "passive"))
      (node (ref "FL221") (pin "1") (pinfunction "IN_1") (pintype "passive"))
      (node (ref "L126") (pin "2") (pinfunction "2_2") (pintype "passive"))
      (node (ref "R390") (pin "2") (pintype "passive"))
    )
    (net (code "31") (name "Net-(FL221-OUT)") (class "Default")
      (node (ref "C426") (pin "2") (pintype "passive"))
      (node (ref "C485") (pin "2") (pintype "passive"))
      (node (ref "FL221") (pin "3") (pinfunction "OUT_3") (pintype "passive"))
      (node (ref "FL222") (pin "1") (pinfunction "IN_1") (pintype "passive"))
    )
    (net (code "32") (name "Net-(FL222-OUT)") (class "Default")
      (node (ref "C482") (pin "1") (pintype "passive"))
      (node (ref "C534") (pin "2") (pintype "passive"))
      (node (ref "FL222") (pin "3") (pinfunction "OUT_3") (pintype "passive"))
      (node (ref "R55") (pin "1") (pintype "passive"))
    )
    (net (code "33") (name "Net-(FL233-IN)") (class "Default")
      (node (ref "FL233") (pin "1") (pinfunction "IN_1") (pintype "passive"))
      (node (ref "U168") (pin "1") (pinfunction "INPUT_1") (pintype "passive"))
    )
    (net (code "34") (name "Net-(FL233-OUT)") (class "Default")
      (node (ref "AT23") (pin "3") (pinfunction "IN/OUT_3") (pintype "passive"))
      (node (ref "FL233") (pin "3") (pinfunction "OUT_3") (pintype "passive"))
    )
    (net (code "35") (name "Net-(FL256-OUT)") (class "Default")
      (node (ref "C420") (pin "1") (pintype "passive"))
      (node (ref "FL256") (pin "3") (pinfunction "OUT_3") (pintype "passive"))
      (node (ref "R253") (pin "1") (pintype "passive"))
    )
    (net (code "36") (name "Net-(FL257-OUT)") (class "Default")
      (node (ref "C533") (pin "1") (pintype "passive"))
      (node (ref "FL257") (pin "3") (pinfunction "OUT_3") (pintype "passive"))
      (node (ref "L147") (pin "2") (pinfunction "2_2") (pintype "passive"))
    )
    (net (code "37") (name "Net-(FL261-OUT)") (class "Default")
      (node (ref "C429") (pin "1") (pintype "passive"))
      (node (ref "FL261") (pin "3") (pinfunction "OUT_3") (pintype "passive"))
      (node (ref "FL262") (pin "1") (pinfunction "IN_1") (pintype "passive"))
    )
    (net (code "38") (name "Net-(FL262-OUT)") (class "Default")
      (node (ref "C430") (pin "1") (pintype "passive"))
      (node (ref "FL262") (pin "3") (pinfunction "OUT_3") (pintype "passive"))
      (node (ref "R457") (pin "2") (pintype "passive"))
    )
    (net (code "39") (name "Net-(FL263-IN)") (class "Default")
      (node (ref "AT63") (pin "3") (pinfunction "IN/OUT_3") (pintype "passive"))
      (node (ref "FL263") (pin "1") (pinfunction "IN_1") (pintype "passive"))
    )
    (net (code "40") (name "Net-(FL263-OUT)") (class "Default")
      (node (ref "AT24") (pin "1") (pinfunction "IN/OUT_1") (pintype "passive"))
      (node (ref "FL263") (pin "3") (pinfunction "OUT_3") (pintype "passive"))
    )
    (net (code "41") (name "Net-(FL264-IN)") (class "Default")
      (node (ref "AT24") (pin "3") (pinfunction "IN/OUT_3") (pintype "passive"))
      (node (ref "FL264") (pin "1") (pinfunction "IN_1") (pintype "passive"))
    )
    (net (code "42") (name "Net-(FL264-OUT)") (class "Default")
      (node (ref "FL264") (pin "3") (pinfunction "OUT_3") (pintype "passive"))
      (node (ref "U68") (pin "2") (pintype "passive"))
    )
    (net (code "43") (name "Net-(J10-Pad1)") (class "Default")
      (node (ref "J10") (pin "1") (pinfunction "1_1") (pintype "passive"))
      (node (ref "U69") (pin "3") (pinfunction "3_3") (pintype "passive"))
    )
    (net (code "44") (name "Net-(J20-CNTR)") (class "Default")
      (node (ref "AT66") (pin "3") (pinfunction "IN/OUT_3") (pintype "passive"))
      (node (ref "J20") (pin "1") (pinfunction "CNTR_1") (pintype "passive"))
    )
    (net (code "45") (name "Net-(R262-Pad2)") (class "Default")
      (node (ref "R262") (pin "2") (pintype "passive"))
      (node (ref "R263") (pin "1") (pintype "passive"))
      (node (ref "U69") (pin "6") (pinfunction "6_6") (pintype "passive"))
    )
    (net (code "46") (name "Net-(R264-Pad2)") (class "Default")
      (node (ref "R264") (pin "2") (pintype "passive"))
      (node (ref "R265") (pin "1") (pintype "passive"))
      (node (ref "U71") (pin "6") (pinfunction "6_6") (pintype "passive"))
    )
    (net (code "47") (name "Net-(R266-Pad2)") (class "Default")
      (node (ref "R266") (pin "2") (pintype "passive"))
      (node (ref "R267") (pin "1") (pintype "passive"))
      (node (ref "U72") (pin "6") (pinfunction "6_6") (pintype "passive"))
    )
    (net (code "48") (name "Net-(U66-RF_IN)") (class "Default")
      (node (ref "C425") (pin "2") (pintype "passive"))
      (node (ref "U66") (pin "1") (pinfunction "RF_IN_1") (pintype "input"))
    )
    (net (code "49") (name "Net-(U66-RF_OUT)") (class "Default")
      (node (ref "C421") (pin "2") (pintype "passive"))
      (node (ref "L147") (pin "1") (pinfunction "1_1") (pintype "passive"))
      (node (ref "U66") (pin "3") (pinfunction "RF_OUT_3") (pintype "output"))
    )
    (net (code "50") (name "Net-(U67-IN)") (class "Default")
      (node (ref "AT67") (pin "3") (pinfunction "IN/OUT_3") (pintype "passive"))
      (node (ref "U67") (pin "4") (pinfunction "IN_4") (pintype "passive"))
    )
    (net (code "51") (name "Net-(U67-TERM)") (class "Default")
      (node (ref "R257") (pin "2") (pintype "passive"))
      (node (ref "U67") (pin "2") (pinfunction "TERM_2") (pintype "passive"))
    )
    (net (code "52") (name "Net-(U71-Pad4)") (class "Default")
      (node (ref "U71") (pin "4") (pinfunction "4_4") (pintype "passive"))
      (node (ref "U72") (pin "3") (pinfunction "3_3") (pintype "passive"))
    )
    (net (code "53") (name "Net-(U120-RF_IN)") (class "Default")
      (node (ref "C164") (pin "2") (pintype "passive"))
      (node (ref "U120") (pin "1") (pinfunction "RF_IN_1") (pintype "input"))
    )
    (net (code "54") (name "Net-(U120-RF_OUT)") (class "Default")
      (node (ref "C165") (pin "1") (pintype "passive"))
      (node (ref "L148") (pin "1") (pinfunction "1_1") (pintype "passive"))
      (node (ref "U120") (pin "3") (pinfunction "RF_OUT_3") (pintype "output"))
    )
    (net (code "55") (name "Net-(U168-CPL_(FWD))") (class "Default")
      (node (ref "AT66") (pin "1") (pinfunction "IN/OUT_1") (pintype "passive"))
      (node (ref "U168") (pin "6") (pinfunction "CPL_(FWD)_6") (pintype "passive"))
    )
    (net (code "56") (name "Net-(U168-CPV_(REV))") (class "Default")
      (node (ref "R780") (pin "2") (pintype "passive"))
      (node (ref "U168") (pin "3") (pinfunction "CPV_(REV)_3") (pintype "passive"))
    )
  )
)
